# avr-fusebit-doctor-enhanced.net
KiCad netlist of a schematic drawn in EAGLE
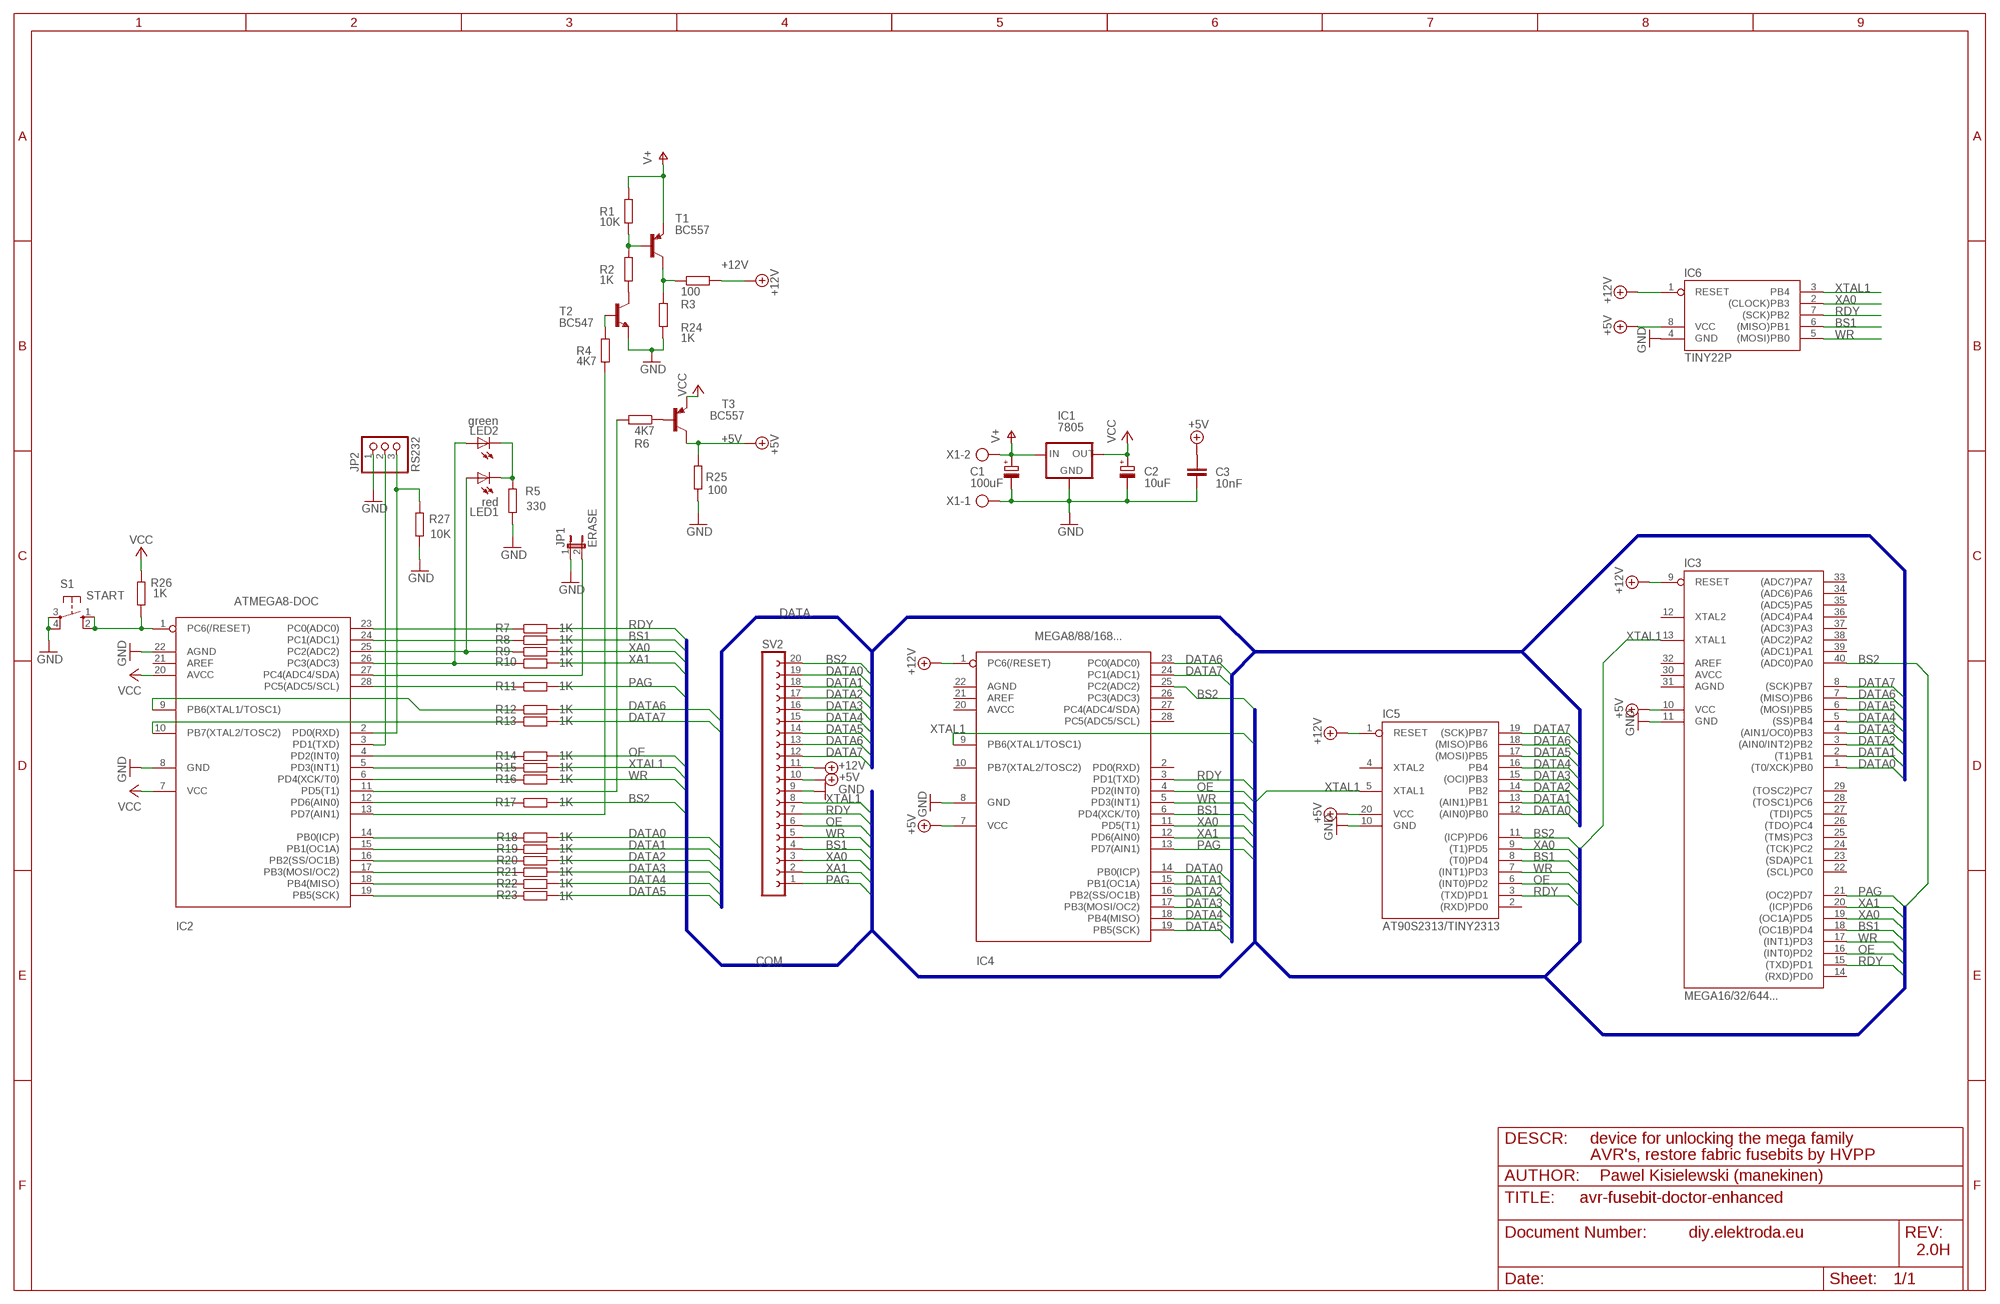
[diagram p0: schematic, sheet 1]

(export (version "E")
  (design (tool "Eeschema 10.0.6"))
  (components
    (comp (ref "C1")
      (value "100uF")
      (footprint "eagle-import:E2,5-5")
      (libsource (lib "eagle-import") (part "CPOL-EUE2.5-5"))
    )
    (comp (ref "C2")
      (value "10uF")
      (footprint "eagle-import:E2,5-5")
      (libsource (lib "eagle-import") (part "CPOL-EUE2.5-5"))
    )
    (comp (ref "C3")
      (value "10nF")
      (footprint "eagle-import:C050-024X044")
      (libsource (lib "eagle-import") (part "C-EU050-024X044"))
    )
    (comp (ref "IC1")
      (value "7805")
      (footprint "eagle-import:78XXL")
      (libsource (lib "eagle-import") (part "78XXL"))
    )
    (comp (ref "IC2")
      (value "ATMEGA8-DOC")
      (footprint "eagle-import:DIL28-3")
      (libsource (lib "eagle-import") (part "MEGA8-P"))
    )
    (comp (ref "IC3")
      (value "MEGA16/32/644...")
      (footprint "eagle-import:DIL40")
      (libsource (lib "eagle-import") (part "MEGA16-P"))
    )
    (comp (ref "IC4")
      (value "MEGA8/88/168...")
      (footprint "eagle-import:DIL28-3")
      (libsource (lib "eagle-import") (part "MEGA8-P"))
    )
    (comp (ref "IC5")
      (value "AT90S2313/TINY2313")
      (footprint "eagle-import:DIL20")
      (libsource (lib "eagle-import") (part "AT90S2313P"))
    )
    (comp (ref "IC6")
      (value "TINY22P")
      (footprint "eagle-import:DIL08")
      (libsource (lib "eagle-import") (part "TINY22P"))
    )
    (comp (ref "JP1")
      (value "ERASE")
      (footprint "eagle-import:JP1")
      (libsource (lib "eagle-import") (part "JP1E"))
    )
    (comp (ref "JP2")
      (value "RS232")
      (footprint "eagle-import:1X03")
      (libsource (lib "eagle-import") (part "PINHD-1X3"))
    )
    (comp (ref "LED1")
      (value "red")
      (footprint "eagle-import:LED3MM")
      (libsource (lib "eagle-import") (part "LED3MM"))
    )
    (comp (ref "LED2")
      (value "green")
      (footprint "eagle-import:LED3MM")
      (libsource (lib "eagle-import") (part "LED3MM"))
    )
    (comp (ref "R1")
      (value "10K")
      (footprint "eagle-import:0204_5")
      (libsource (lib "eagle-import") (part "R-EU_0204/5"))
    )
    (comp (ref "R2")
      (value "1K")
      (footprint "eagle-import:0204_5")
      (libsource (lib "eagle-import") (part "R-EU_0204/5"))
    )
    (comp (ref "R3")
      (value "100")
      (footprint "eagle-import:0204_5")
      (libsource (lib "eagle-import") (part "R-EU_0204/5"))
    )
    (comp (ref "R4")
      (value "4K7")
      (footprint "eagle-import:0204_5")
      (libsource (lib "eagle-import") (part "R-EU_0204/5"))
    )
    (comp (ref "R5")
      (value "330")
      (footprint "eagle-import:0204_5")
      (libsource (lib "eagle-import") (part "R-EU_0204/5"))
    )
    (comp (ref "R6")
      (value "4K7")
      (footprint "eagle-import:0204_5")
      (libsource (lib "eagle-import") (part "R-EU_0204/5"))
    )
    (comp (ref "R7")
      (value "1K")
      (footprint "eagle-import:0204_5")
      (libsource (lib "eagle-import") (part "R-EU_0204/5"))
    )
    (comp (ref "R8")
      (value "1K")
      (footprint "eagle-import:0204_5")
      (libsource (lib "eagle-import") (part "R-EU_0204/5"))
    )
    (comp (ref "R9")
      (value "1K")
      (footprint "eagle-import:0204_5")
      (libsource (lib "eagle-import") (part "R-EU_0204/5"))
    )
    (comp (ref "R10")
      (value "1K")
      (footprint "eagle-import:0204_5")
      (libsource (lib "eagle-import") (part "R-EU_0204/5"))
    )
    (comp (ref "R11")
      (value "1K")
      (footprint "eagle-import:0204_5")
      (libsource (lib "eagle-import") (part "R-EU_0204/5"))
    )
    (comp (ref "R12")
      (value "1K")
      (footprint "eagle-import:0204_5")
      (libsource (lib "eagle-import") (part "R-EU_0204/5"))
    )
    (comp (ref "R13")
      (value "1K")
      (footprint "eagle-import:0204_5")
      (libsource (lib "eagle-import") (part "R-EU_0204/5"))
    )
    (comp (ref "R14")
      (value "1K")
      (footprint "eagle-import:0204_5")
      (libsource (lib "eagle-import") (part "R-EU_0204/5"))
    )
    (comp (ref "R15")
      (value "1K")
      (footprint "eagle-import:0204_5")
      (libsource (lib "eagle-import") (part "R-EU_0204/5"))
    )
    (comp (ref "R16")
      (value "1K")
      (footprint "eagle-import:0204_5")
      (libsource (lib "eagle-import") (part "R-EU_0204/5"))
    )
    (comp (ref "R17")
      (value "1K")
      (footprint "eagle-import:0204_5")
      (libsource (lib "eagle-import") (part "R-EU_0204/5"))
    )
    (comp (ref "R18")
      (value "1K")
      (footprint "eagle-import:0204_5")
      (libsource (lib "eagle-import") (part "R-EU_0204/5"))
    )
    (comp (ref "R19")
      (value "1K")
      (footprint "eagle-import:0204_5")
      (libsource (lib "eagle-import") (part "R-EU_0204/5"))
    )
    (comp (ref "R20")
      (value "1K")
      (footprint "eagle-import:0204_5")
      (libsource (lib "eagle-import") (part "R-EU_0204/5"))
    )
    (comp (ref "R21")
      (value "1K")
      (footprint "eagle-import:0204_5")
      (libsource (lib "eagle-import") (part "R-EU_0204/5"))
    )
    (comp (ref "R22")
      (value "1K")
      (footprint "eagle-import:0204_5")
      (libsource (lib "eagle-import") (part "R-EU_0204/5"))
    )
    (comp (ref "R23")
      (value "1K")
      (footprint "eagle-import:0204_5")
      (libsource (lib "eagle-import") (part "R-EU_0204/5"))
    )
    (comp (ref "R24")
      (value "1K")
      (footprint "eagle-import:0204_5")
      (libsource (lib "eagle-import") (part "R-EU_0204/5"))
    )
    (comp (ref "R25")
      (value "100")
      (footprint "eagle-import:0204_5")
      (libsource (lib "eagle-import") (part "R-EU_0204/5"))
    )
    (comp (ref "R26")
      (value "1K")
      (footprint "eagle-import:0204_5")
      (libsource (lib "eagle-import") (part "R-EU_0204/5"))
    )
    (comp (ref "R27")
      (value "10K")
      (footprint "eagle-import:0204_5")
      (libsource (lib "eagle-import") (part "R-EU_0204/5"))
    )
    (comp (ref "S1")
      (value "START")
      (footprint "eagle-import:B3F-10XX")
      (libsource (lib "eagle-import") (part "10-XX"))
    )
    (comp (ref "SV2")
      (value "FE20-1")
      (footprint "eagle-import:FE20")
      (libsource (lib "eagle-import") (part "FE20-1"))
    )
    (comp (ref "T1")
      (value "BC557")
      (footprint "eagle-import:TO92-EBC")
      (libsource (lib "eagle-import") (part "-PNP-TO92-EBCBC557C"))
    )
    (comp (ref "T2")
      (value "BC547")
      (footprint "eagle-import:TO92-EBC")
      (libsource (lib "eagle-import") (part "-NPN-TO92-EBCBC547A"))
    )
    (comp (ref "T3")
      (value "BC557")
      (footprint "eagle-import:TO92-EBC")
      (libsource (lib "eagle-import") (part "-PNP-TO92-EBCBC557C"))
    )
    (comp (ref "X1")
      (value "AK500/2")
      (footprint "eagle-import:AK500_2")
      (libsource (lib "eagle-import") (part "AK500/2"))
    )
  )
  (nets
    (net (code "3") (name "+5V") (class "Default")
      (node (ref "C3") (pin "1") (pinfunction "1_1") (pintype "passive"))
      (node (ref "IC3") (pin "10") (pinfunction "VCC_10") (pintype "power_in"))
      (node (ref "IC4") (pin "7") (pinfunction "VCC_7") (pintype "bidirectional"))
      (node (ref "IC5") (pin "20") (pinfunction "VCC_20") (pintype "power_in"))
      (node (ref "IC6") (pin "8") (pinfunction "VCC_8") (pintype "power_in"))
      (node (ref "R25") (pin "2") (pinfunction "2_2") (pintype "passive"))
      (node (ref "SV2") (pin "10") (pinfunction "10_10") (pintype "passive"))
      (node (ref "T3") (pin "C") (pinfunction "C_C") (pintype "passive"))
    )
    (net (code "4") (name "+12V") (class "Default")
      (node (ref "IC3") (pin "9") (pinfunction "RESET_9") (pintype "input"))
      (node (ref "IC4") (pin "1") (pinfunction "PC6(/RESET)_1") (pintype "bidirectional"))
      (node (ref "IC5") (pin "1") (pinfunction "RESET_1") (pintype "bidirectional"))
      (node (ref "IC6") (pin "1") (pinfunction "RESET_1") (pintype "input"))
      (node (ref "R3") (pin "2") (pinfunction "2_2") (pintype "passive"))
      (node (ref "SV2") (pin "11") (pinfunction "11_11") (pintype "passive"))
    )
    (net (code "5") (name "/AGND") (class "Default")
      (node (ref "IC3") (pin "31") (pinfunction "AGND_31") (pintype "power_in"))
    )
    (net (code "6") (name "/AREF") (class "Default")
      (node (ref "IC3") (pin "32") (pinfunction "AREF_32") (pintype "power_in"))
    )
    (net (code "7") (name "/AVCC") (class "Default")
      (node (ref "IC3") (pin "30") (pinfunction "AVCC_30") (pintype "power_in"))
    )
    (net (code "8") (name "/BS1") (class "Default")
      (node (ref "IC3") (pin "18") (pinfunction "(OC1B)PD4_18") (pintype "bidirectional"))
      (node (ref "IC4") (pin "6") (pinfunction "PD4(XCK/T0)_6") (pintype "bidirectional"))
      (node (ref "IC5") (pin "8") (pinfunction "(T0)PD4_8") (pintype "bidirectional"))
      (node (ref "IC6") (pin "6") (pinfunction "(MISO)PB1_6") (pintype "bidirectional"))
      (node (ref "R8") (pin "2") (pinfunction "2_2") (pintype "passive"))
      (node (ref "SV2") (pin "4") (pinfunction "4_4") (pintype "passive"))
    )
    (net (code "9") (name "/BS2") (class "Default")
      (node (ref "IC3") (pin "40") (pinfunction "(ADC0)PA0_40") (pintype "bidirectional"))
      (node (ref "IC4") (pin "25") (pinfunction "PC2(ADC2)_25") (pintype "bidirectional"))
      (node (ref "IC5") (pin "11") (pinfunction "(ICP)PD6_11") (pintype "bidirectional"))
      (node (ref "R17") (pin "2") (pinfunction "2_2") (pintype "passive"))
      (node (ref "SV2") (pin "20") (pinfunction "20_20") (pintype "passive"))
    )
    (net (code "10") (name "/DATA0") (class "Default")
      (node (ref "IC3") (pin "1") (pinfunction "(T0/XCK)PB0_1") (pintype "bidirectional"))
      (node (ref "IC4") (pin "14") (pinfunction "PB0(ICP)_14") (pintype "bidirectional"))
      (node (ref "IC5") (pin "12") (pinfunction "(AIN0)PB0_12") (pintype "bidirectional"))
      (node (ref "R18") (pin "2") (pinfunction "2_2") (pintype "passive"))
      (node (ref "SV2") (pin "19") (pinfunction "19_19") (pintype "passive"))
    )
    (net (code "11") (name "/DATA1") (class "Default")
      (node (ref "IC3") (pin "2") (pinfunction "(T1)PB1_2") (pintype "bidirectional"))
      (node (ref "IC4") (pin "15") (pinfunction "PB1(OC1A)_15") (pintype "bidirectional"))
      (node (ref "IC5") (pin "13") (pinfunction "(AIN1)PB1_13") (pintype "bidirectional"))
      (node (ref "R19") (pin "2") (pinfunction "2_2") (pintype "passive"))
      (node (ref "SV2") (pin "18") (pinfunction "18_18") (pintype "passive"))
    )
    (net (code "12") (name "/DATA2") (class "Default")
      (node (ref "IC3") (pin "3") (pinfunction "(AIN0/INT2)PB2_3") (pintype "bidirectional"))
      (node (ref "IC4") (pin "16") (pinfunction "PB2(SS/OC1B)_16") (pintype "bidirectional"))
      (node (ref "IC5") (pin "14") (pinfunction "PB2_14") (pintype "bidirectional"))
      (node (ref "R20") (pin "2") (pinfunction "2_2") (pintype "passive"))
      (node (ref "SV2") (pin "17") (pinfunction "17_17") (pintype "passive"))
    )
    (net (code "13") (name "/DATA3") (class "Default")
      (node (ref "IC3") (pin "4") (pinfunction "(AIN1/OC0)PB3_4") (pintype "bidirectional"))
      (node (ref "IC4") (pin "17") (pinfunction "PB3(MOSI/OC2)_17") (pintype "bidirectional"))
      (node (ref "IC5") (pin "15") (pinfunction "(OCI)PB3_15") (pintype "bidirectional"))
      (node (ref "R21") (pin "2") (pinfunction "2_2") (pintype "passive"))
      (node (ref "SV2") (pin "16") (pinfunction "16_16") (pintype "passive"))
    )
    (net (code "14") (name "/DATA4") (class "Default")
      (node (ref "IC3") (pin "5") (pinfunction "(SS)PB4_5") (pintype "bidirectional"))
      (node (ref "IC4") (pin "18") (pinfunction "PB4(MISO)_18") (pintype "bidirectional"))
      (node (ref "IC5") (pin "16") (pinfunction "PB4_16") (pintype "bidirectional"))
      (node (ref "R22") (pin "2") (pinfunction "2_2") (pintype "passive"))
      (node (ref "SV2") (pin "15") (pinfunction "15_15") (pintype "passive"))
    )
    (net (code "15") (name "/DATA5") (class "Default")
      (node (ref "IC3") (pin "6") (pinfunction "(MOSI)PB5_6") (pintype "bidirectional"))
      (node (ref "IC4") (pin "19") (pinfunction "PB5(SCK)_19") (pintype "bidirectional"))
      (node (ref "IC5") (pin "17") (pinfunction "(MOSI)PB5_17") (pintype "bidirectional"))
      (node (ref "R23") (pin "2") (pinfunction "2_2") (pintype "passive"))
      (node (ref "SV2") (pin "14") (pinfunction "14_14") (pintype "passive"))
    )
    (net (code "16") (name "/DATA6") (class "Default")
      (node (ref "IC3") (pin "7") (pinfunction "(MISO)PB6_7") (pintype "bidirectional"))
      (node (ref "IC4") (pin "23") (pinfunction "PC0(ADC0)_23") (pintype "bidirectional"))
      (node (ref "IC5") (pin "18") (pinfunction "(MISO)PB6_18") (pintype "bidirectional"))
      (node (ref "R12") (pin "2") (pinfunction "2_2") (pintype "passive"))
      (node (ref "SV2") (pin "13") (pinfunction "13_13") (pintype "passive"))
    )
    (net (code "17") (name "/DATA7") (class "Default")
      (node (ref "IC3") (pin "8") (pinfunction "(SCK)PB7_8") (pintype "bidirectional"))
      (node (ref "IC4") (pin "24") (pinfunction "PC1(ADC1)_24") (pintype "bidirectional"))
      (node (ref "IC5") (pin "19") (pinfunction "(SCK)PB7_19") (pintype "bidirectional"))
      (node (ref "R13") (pin "2") (pinfunction "2_2") (pintype "passive"))
      (node (ref "SV2") (pin "12") (pinfunction "12_12") (pintype "passive"))
    )
    (net (code "18") (name "/OE") (class "Default")
      (node (ref "IC3") (pin "16") (pinfunction "(INT0)PD2_16") (pintype "bidirectional"))
      (node (ref "IC4") (pin "4") (pinfunction "PD2(INT0)_4") (pintype "bidirectional"))
      (node (ref "IC5") (pin "6") (pinfunction "(INT0)PD2_6") (pintype "bidirectional"))
      (node (ref "R14") (pin "2") (pinfunction "2_2") (pintype "passive"))
      (node (ref "SV2") (pin "6") (pinfunction "6_6") (pintype "passive"))
    )
    (net (code "19") (name "/PAG") (class "Default")
      (node (ref "IC3") (pin "21") (pinfunction "(OC2)PD7_21") (pintype "bidirectional"))
      (node (ref "IC4") (pin "13") (pinfunction "PD7(AIN1)_13") (pintype "bidirectional"))
      (node (ref "R11") (pin "2") (pinfunction "2_2") (pintype "passive"))
      (node (ref "SV2") (pin "1") (pinfunction "1_1") (pintype "passive"))
    )
    (net (code "20") (name "/RDY") (class "Default")
      (node (ref "IC3") (pin "15") (pinfunction "(TXD)PD1_15") (pintype "bidirectional"))
      (node (ref "IC4") (pin "3") (pinfunction "PD1(TXD)_3") (pintype "bidirectional"))
      (node (ref "IC5") (pin "3") (pinfunction "(TXD)PD1_3") (pintype "bidirectional"))
      (node (ref "IC6") (pin "7") (pinfunction "(SCK)PB2_7") (pintype "bidirectional"))
      (node (ref "R7") (pin "2") (pinfunction "2_2") (pintype "passive"))
      (node (ref "SV2") (pin "7") (pinfunction "7_7") (pintype "passive"))
    )
    (net (code "21") (name "/WR") (class "Default")
      (node (ref "IC3") (pin "17") (pinfunction "(INT1)PD3_17") (pintype "bidirectional"))
      (node (ref "IC4") (pin "5") (pinfunction "PD3(INT1)_5") (pintype "bidirectional"))
      (node (ref "IC5") (pin "7") (pinfunction "(INT1)PD3_7") (pintype "bidirectional"))
      (node (ref "IC6") (pin "5") (pinfunction "(MOSI)PB0_5") (pintype "bidirectional"))
      (node (ref "R16") (pin "2") (pinfunction "2_2") (pintype "passive"))
      (node (ref "SV2") (pin "5") (pinfunction "5_5") (pintype "passive"))
    )
    (net (code "22") (name "/XA0") (class "Default")
      (node (ref "IC3") (pin "19") (pinfunction "(OC1A)PD5_19") (pintype "bidirectional"))
      (node (ref "IC4") (pin "11") (pinfunction "PD5(T1)_11") (pintype "bidirectional"))
      (node (ref "IC5") (pin "9") (pinfunction "(T1)PD5_9") (pintype "bidirectional"))
      (node (ref "IC6") (pin "2") (pinfunction "(CLOCK)PB3_2") (pintype "bidirectional"))
      (node (ref "R9") (pin "2") (pinfunction "2_2") (pintype "passive"))
      (node (ref "SV2") (pin "3") (pinfunction "3_3") (pintype "passive"))
    )
    (net (code "23") (name "/XA1") (class "Default")
      (node (ref "IC3") (pin "20") (pinfunction "(ICP)PD6_20") (pintype "bidirectional"))
      (node (ref "IC4") (pin "12") (pinfunction "PD6(AIN0)_12") (pintype "bidirectional"))
      (node (ref "R10") (pin "2") (pinfunction "2_2") (pintype "passive"))
      (node (ref "SV2") (pin "2") (pinfunction "2_2") (pintype "passive"))
    )
    (net (code "24") (name "/XTAL1") (class "Default")
      (node (ref "IC3") (pin "13") (pinfunction "XTAL1_13") (pintype "bidirectional"))
      (node (ref "IC4") (pin "9") (pinfunction "PB6(XTAL1/TOSC1)_9") (pintype "bidirectional"))
      (node (ref "IC5") (pin "5") (pinfunction "XTAL1_5") (pintype "bidirectional"))
      (node (ref "IC6") (pin "3") (pinfunction "PB4_3") (pintype "bidirectional"))
      (node (ref "R15") (pin "2") (pinfunction "2_2") (pintype "passive"))
      (node (ref "SV2") (pin "8") (pinfunction "8_8") (pintype "passive"))
    )
    (net (code "27") (name "GND") (class "Default")
      (node (ref "C1") (pin "-") (pinfunction "-_-") (pintype "passive"))
      (node (ref "C2") (pin "-") (pinfunction "-_-") (pintype "passive"))
      (node (ref "C3") (pin "2") (pinfunction "2_2") (pintype "passive"))
      (node (ref "IC1") (pin "GND") (pinfunction "GND_GND") (pintype "input"))
      (node (ref "IC2") (pin "22") (pinfunction "AGND_22") (pintype "bidirectional"))
      (node (ref "IC2") (pin "8") (pinfunction "GND_8") (pintype "bidirectional"))
      (node (ref "IC3") (pin "11") (pinfunction "GND_11") (pintype "power_in"))
      (node (ref "IC4") (pin "8") (pinfunction "GND_8") (pintype "bidirectional"))
      (node (ref "IC5") (pin "10") (pinfunction "GND_10") (pintype "power_in"))
      (node (ref "IC6") (pin "4") (pinfunction "GND_4") (pintype "power_in"))
      (node (ref "JP1") (pin "1") (pinfunction "1_1") (pintype "passive"))
      (node (ref "JP2") (pin "1") (pinfunction "1_1") (pintype "passive"))
      (node (ref "R24") (pin "1") (pinfunction "1_1") (pintype "passive"))
      (node (ref "R25") (pin "1") (pinfunction "1_1") (pintype "passive"))
      (node (ref "R27") (pin "2") (pinfunction "2_2") (pintype "passive"))
      (node (ref "R5") (pin "1") (pinfunction "1_1") (pintype "passive"))
      (node (ref "S1") (pin "3") (pinfunction "P_3") (pintype "passive"))
      (node (ref "S1") (pin "4") (pinfunction "P1_4") (pintype "passive"))
      (node (ref "SV2") (pin "9") (pinfunction "9_9") (pintype "passive"))
      (node (ref "T2") (pin "E") (pinfunction "E_E") (pintype "passive"))
      (node (ref "X1") (pin "1") (pinfunction "KL_1") (pintype "passive"))
    )
    (net (code "28") (name "Net-(IC2-PB0(ICP))") (class "Default")
      (node (ref "IC2") (pin "14") (pinfunction "PB0(ICP)_14") (pintype "bidirectional"))
      (node (ref "R18") (pin "1") (pinfunction "1_1") (pintype "passive"))
    )
    (net (code "29") (name "Net-(IC2-PB1(OC1A))") (class "Default")
      (node (ref "IC2") (pin "15") (pinfunction "PB1(OC1A)_15") (pintype "bidirectional"))
      (node (ref "R19") (pin "1") (pinfunction "1_1") (pintype "passive"))
    )
    (net (code "30") (name "Net-(IC2-PB2(SS{slash}OC1B))") (class "Default")
      (node (ref "IC2") (pin "16") (pinfunction "PB2(SS/OC1B)_16") (pintype "bidirectional"))
      (node (ref "R20") (pin "1") (pinfunction "1_1") (pintype "passive"))
    )
    (net (code "31") (name "Net-(IC2-PB3(MOSI{slash}OC2))") (class "Default")
      (node (ref "IC2") (pin "17") (pinfunction "PB3(MOSI/OC2)_17") (pintype "bidirectional"))
      (node (ref "R21") (pin "1") (pinfunction "1_1") (pintype "passive"))
    )
    (net (code "32") (name "Net-(IC2-PB4(MISO))") (class "Default")
      (node (ref "IC2") (pin "18") (pinfunction "PB4(MISO)_18") (pintype "bidirectional"))
      (node (ref "R22") (pin "1") (pinfunction "1_1") (pintype "passive"))
    )
    (net (code "33") (name "Net-(IC2-PB5(SCK))") (class "Default")
      (node (ref "IC2") (pin "19") (pinfunction "PB5(SCK)_19") (pintype "bidirectional"))
      (node (ref "R23") (pin "1") (pinfunction "1_1") (pintype "passive"))
    )
    (net (code "34") (name "Net-(IC2-PB6(XTAL1{slash}TOSC1))") (class "Default")
      (node (ref "IC2") (pin "9") (pinfunction "PB6(XTAL1/TOSC1)_9") (pintype "bidirectional"))
      (node (ref "R12") (pin "1") (pinfunction "1_1") (pintype "passive"))
    )
    (net (code "35") (name "Net-(IC2-PB7(XTAL2{slash}TOSC2))") (class "Default")
      (node (ref "IC2") (pin "10") (pinfunction "PB7(XTAL2/TOSC2)_10") (pintype "bidirectional"))
      (node (ref "R13") (pin "1") (pinfunction "1_1") (pintype "passive"))
    )
    (net (code "36") (name "Net-(IC2-PC0(ADC0))") (class "Default")
      (node (ref "IC2") (pin "23") (pinfunction "PC0(ADC0)_23") (pintype "bidirectional"))
      (node (ref "R7") (pin "1") (pinfunction "1_1") (pintype "passive"))
    )
    (net (code "37") (name "Net-(IC2-PC1(ADC1))") (class "Default")
      (node (ref "IC2") (pin "24") (pinfunction "PC1(ADC1)_24") (pintype "bidirectional"))
      (node (ref "R8") (pin "1") (pinfunction "1_1") (pintype "passive"))
    )
    (net (code "38") (name "Net-(IC2-PC2(ADC2))") (class "Default")
      (node (ref "IC2") (pin "25") (pinfunction "PC2(ADC2)_25") (pintype "bidirectional"))
      (node (ref "LED1") (pin "A") (pinfunction "A_A") (pintype "passive"))
      (node (ref "R9") (pin "1") (pinfunction "1_1") (pintype "passive"))
    )
    (net (code "39") (name "Net-(IC2-PC3(ADC3))") (class "Default")
      (node (ref "IC2") (pin "26") (pinfunction "PC3(ADC3)_26") (pintype "bidirectional"))
      (node (ref "LED2") (pin "A") (pinfunction "A_A") (pintype "passive"))
      (node (ref "R10") (pin "1") (pinfunction "1_1") (pintype "passive"))
    )
    (net (code "40") (name "Net-(IC2-PC4(ADC4{slash}SDA))") (class "Default")
      (node (ref "IC2") (pin "27") (pinfunction "PC4(ADC4/SDA)_27") (pintype "bidirectional"))
      (node (ref "JP1") (pin "2") (pinfunction "2_2") (pintype "passive"))
    )
    (net (code "41") (name "Net-(IC2-PC5(ADC5{slash}SCL))") (class "Default")
      (node (ref "IC2") (pin "28") (pinfunction "PC5(ADC5/SCL)_28") (pintype "bidirectional"))
      (node (ref "R11") (pin "1") (pinfunction "1_1") (pintype "passive"))
    )
    (net (code "42") (name "Net-(IC2-PC6({slash}RESET))") (class "Default")
      (node (ref "IC2") (pin "1") (pinfunction "PC6(/RESET)_1") (pintype "bidirectional"))
      (node (ref "R26") (pin "1") (pinfunction "1_1") (pintype "passive"))
      (node (ref "S1") (pin "1") (pinfunction "S_1") (pintype "passive"))
      (node (ref "S1") (pin "2") (pinfunction "S1_2") (pintype "passive"))
    )
    (net (code "43") (name "Net-(IC2-PD0(RXD))") (class "Default")
      (node (ref "IC2") (pin "2") (pinfunction "PD0(RXD)_2") (pintype "bidirectional"))
      (node (ref "JP2") (pin "3") (pinfunction "3_3") (pintype "passive"))
      (node (ref "R27") (pin "1") (pinfunction "1_1") (pintype "passive"))
    )
    (net (code "44") (name "Net-(IC2-PD1(TXD))") (class "Default")
      (node (ref "IC2") (pin "3") (pinfunction "PD1(TXD)_3") (pintype "bidirectional"))
      (node (ref "JP2") (pin "2") (pinfunction "2_2") (pintype "passive"))
    )
    (net (code "45") (name "Net-(IC2-PD2(INT0))") (class "Default")
      (node (ref "IC2") (pin "4") (pinfunction "PD2(INT0)_4") (pintype "bidirectional"))
      (node (ref "R14") (pin "1") (pinfunction "1_1") (pintype "passive"))
    )
    (net (code "46") (name "Net-(IC2-PD3(INT1))") (class "Default")
      (node (ref "IC2") (pin "5") (pinfunction "PD3(INT1)_5") (pintype "bidirectional"))
      (node (ref "R15") (pin "1") (pinfunction "1_1") (pintype "passive"))
    )
    (net (code "47") (name "Net-(IC2-PD4(XCK{slash}T0))") (class "Default")
      (node (ref "IC2") (pin "6") (pinfunction "PD4(XCK/T0)_6") (pintype "bidirectional"))
      (node (ref "R16") (pin "1") (pinfunction "1_1") (pintype "passive"))
    )
    (net (code "48") (name "Net-(IC2-PD5(T1))") (class "Default")
      (node (ref "IC2") (pin "11") (pinfunction "PD5(T1)_11") (pintype "bidirectional"))
      (node (ref "R6") (pin "2") (pinfunction "2_2") (pintype "passive"))
    )
    (net (code "49") (name "Net-(IC2-PD6(AIN0))") (class "Default")
      (node (ref "IC2") (pin "12") (pinfunction "PD6(AIN0)_12") (pintype "bidirectional"))
      (node (ref "R17") (pin "1") (pinfunction "1_1") (pintype "passive"))
    )
    (net (code "50") (name "Net-(IC2-PD7(AIN1))") (class "Default")
      (node (ref "IC2") (pin "13") (pinfunction "PD7(AIN1)_13") (pintype "bidirectional"))
      (node (ref "R4") (pin "2") (pinfunction "2_2") (pintype "passive"))
    )
    (net (code "51") (name "Net-(LED1-C)") (class "Default")
      (node (ref "LED1") (pin "K") (pinfunction "C_K") (pintype "passive"))
      (node (ref "LED2") (pin "K") (pinfunction "C_K") (pintype "passive"))
      (node (ref "R5") (pin "2") (pinfunction "2_2") (pintype "passive"))
    )
    (net (code "52") (name "Net-(R1-Pad2)") (class "Default")
      (node (ref "R1") (pin "2") (pinfunction "2_2") (pintype "passive"))
      (node (ref "R2") (pin "1") (pinfunction "1_1") (pintype "passive"))
      (node (ref "T1") (pin "B") (pinfunction "B_B") (pintype "passive"))
    )
    (net (code "53") (name "Net-(R2-Pad2)") (class "Default")
      (node (ref "R2") (pin "2") (pinfunction "2_2") (pintype "passive"))
      (node (ref "T2") (pin "C") (pinfunction "C_C") (pintype "passive"))
    )
    (net (code "54") (name "Net-(R4-Pad1)") (class "Default")
      (node (ref "R4") (pin "1") (pinfunction "1_1") (pintype "passive"))
      (node (ref "T2") (pin "B") (pinfunction "B_B") (pintype "passive"))
    )
    (net (code "55") (name "Net-(R6-Pad1)") (class "Default")
      (node (ref "R6") (pin "1") (pinfunction "1_1") (pintype "passive"))
      (node (ref "T3") (pin "B") (pinfunction "B_B") (pintype "passive"))
    )
    (net (code "56") (name "Net-(R24-Pad2)") (class "Default")
      (node (ref "R24") (pin "2") (pinfunction "2_2") (pintype "passive"))
      (node (ref "R3") (pin "1") (pinfunction "1_1") (pintype "passive"))
      (node (ref "T1") (pin "C") (pinfunction "C_C") (pintype "passive"))
    )
    (net (code "57") (name "V+") (class "Default")
      (node (ref "C1") (pin "+") (pinfunction "+_+") (pintype "passive"))
      (node (ref "IC1") (pin "IN") (pinfunction "IN_IN") (pintype "input"))
      (node (ref "R1") (pin "1") (pinfunction "1_1") (pintype "passive"))
      (node (ref "T1") (pin "E") (pinfunction "E_E") (pintype "passive"))
      (node (ref "X1") (pin "2") (pinfunction "KL_2") (pintype "passive"))
    )
    (net (code "58") (name "VCC") (class "Default")
      (node (ref "C2") (pin "+") (pinfunction "+_+") (pintype "passive"))
      (node (ref "IC1") (pin "OUT") (pinfunction "OUT_OUT") (pintype "passive"))
      (node (ref "IC2") (pin "20") (pinfunction "AVCC_20") (pintype "bidirectional"))
      (node (ref "IC2") (pin "7") (pinfunction "VCC_7") (pintype "bidirectional"))
      (node (ref "R26") (pin "2") (pinfunction "2_2") (pintype "passive"))
      (node (ref "T3") (pin "E") (pinfunction "E_E") (pintype "passive"))
    )
    (net (code "59") (name "unconnected-(IC2-AREF-Pad21)") (class "Default")
      (node (ref "IC2") (pin "21") (pinfunction "AREF_21") (pintype "bidirectional"))
    )
    (net (code "60") (name "unconnected-(IC3-(ADC1)PA1-Pad39)") (class "Default")
      (node (ref "IC3") (pin "39") (pinfunction "(ADC1)PA1_39") (pintype "bidirectional"))
    )
    (net (code "61") (name "unconnected-(IC3-(ADC2)PA2-Pad38)") (class "Default")
      (node (ref "IC3") (pin "38") (pinfunction "(ADC2)PA2_38") (pintype "bidirectional"))
    )
    (net (code "62") (name "unconnected-(IC3-(ADC3)PA3-Pad37)") (class "Default")
      (node (ref "IC3") (pin "37") (pinfunction "(ADC3)PA3_37") (pintype "bidirectional"))
    )
    (net (code "63") (name "unconnected-(IC3-(ADC4)PA4-Pad36)") (class "Default")
      (node (ref "IC3") (pin "36") (pinfunction "(ADC4)PA4_36") (pintype "bidirectional"))
    )
    (net (code "64") (name "unconnected-(IC3-(ADC5)PA5-Pad35)") (class "Default")
      (node (ref "IC3") (pin "35") (pinfunction "(ADC5)PA5_35") (pintype "bidirectional"))
    )
    (net (code "65") (name "unconnected-(IC3-(ADC6)PA6-Pad34)") (class "Default")
      (node (ref "IC3") (pin "34") (pinfunction "(ADC6)PA6_34") (pintype "bidirectional"))
    )
    (net (code "66") (name "unconnected-(IC3-(ADC7)PA7-Pad33)") (class "Default")
      (node (ref "IC3") (pin "33") (pinfunction "(ADC7)PA7_33") (pintype "bidirectional"))
    )
    (net (code "67") (name "unconnected-(IC3-(RXD)PD0-Pad14)") (class "Default")
      (node (ref "IC3") (pin "14") (pinfunction "(RXD)PD0_14") (pintype "bidirectional"))
    )
    (net (code "68") (name "unconnected-(IC3-(SCL)PC0-Pad22)") (class "Default")
      (node (ref "IC3") (pin "22") (pinfunction "(SCL)PC0_22") (pintype "bidirectional"))
    )
    (net (code "69") (name "unconnected-(IC3-(SDA)PC1-Pad23)") (class "Default")
      (node (ref "IC3") (pin "23") (pinfunction "(SDA)PC1_23") (pintype "bidirectional"))
    )
    (net (code "70") (name "unconnected-(IC3-(TCK)PC2-Pad24)") (class "Default")
      (node (ref "IC3") (pin "24") (pinfunction "(TCK)PC2_24") (pintype "bidirectional"))
    )
    (net (code "71") (name "unconnected-(IC3-(TDI)PC5-Pad27)") (class "Default")
      (node (ref "IC3") (pin "27") (pinfunction "(TDI)PC5_27") (pintype "bidirectional"))
    )
    (net (code "72") (name "unconnected-(IC3-(TDO)PC4-Pad26)") (class "Default")
      (node (ref "IC3") (pin "26") (pinfunction "(TDO)PC4_26") (pintype "bidirectional"))
    )
    (net (code "73") (name "unconnected-(IC3-(TMS)PC3-Pad25)") (class "Default")
      (node (ref "IC3") (pin "25") (pinfunction "(TMS)PC3_25") (pintype "bidirectional"))
    )
    (net (code "74") (name "unconnected-(IC3-(TOSC1)PC6-Pad28)") (class "Default")
      (node (ref "IC3") (pin "28") (pinfunction "(TOSC1)PC6_28") (pintype "bidirectional"))
    )
    (net (code "75") (name "unconnected-(IC3-(TOSC2)PC7-Pad29)") (class "Default")
      (node (ref "IC3") (pin "29") (pinfunction "(TOSC2)PC7_29") (pintype "bidirectional"))
    )
    (net (code "76") (name "unconnected-(IC3-XTAL2-Pad12)") (class "Default")
      (node (ref "IC3") (pin "12") (pinfunction "XTAL2_12") (pintype "bidirectional"))
    )
    (net (code "77") (name "unconnected-(IC4-AGND-Pad22)") (class "Default")
      (node (ref "IC4") (pin "22") (pinfunction "AGND_22") (pintype "bidirectional"))
    )
    (net (code "78") (name "unconnected-(IC4-AREF-Pad21)") (class "Default")
      (node (ref "IC4") (pin "21") (pinfunction "AREF_21") (pintype "bidirectional"))
    )
    (net (code "79") (name "unconnected-(IC4-AVCC-Pad20)") (class "Default")
      (node (ref "IC4") (pin "20") (pinfunction "AVCC_20") (pintype "bidirectional"))
    )
    (net (code "80") (name "unconnected-(IC4-PB7(XTAL2{slash}TOSC2)-Pad10)") (class "Default")
      (node (ref "IC4") (pin "10") (pinfunction "PB7(XTAL2/TOSC2)_10") (pintype "bidirectional"))
    )
    (net (code "81") (name "unconnected-(IC4-PC3(ADC3)-Pad26)") (class "Default")
      (node (ref "IC4") (pin "26") (pinfunction "PC3(ADC3)_26") (pintype "bidirectional"))
    )
    (net (code "82") (name "unconnected-(IC4-PC4(ADC4{slash}SDA)-Pad27)") (class "Default")
      (node (ref "IC4") (pin "27") (pinfunction "PC4(ADC4/SDA)_27") (pintype "bidirectional"))
    )
    (net (code "83") (name "unconnected-(IC4-PC5(ADC5{slash}SCL)-Pad28)") (class "Default")
      (node (ref "IC4") (pin "28") (pinfunction "PC5(ADC5/SCL)_28") (pintype "bidirectional"))
    )
    (net (code "84") (name "unconnected-(IC4-PD0(RXD)-Pad2)") (class "Default")
      (node (ref "IC4") (pin "2") (pinfunction "PD0(RXD)_2") (pintype "bidirectional"))
    )
    (net (code "85") (name "unconnected-(IC5-(RXD)PD0-Pad2)") (class "Default")
      (node (ref "IC5") (pin "2") (pinfunction "(RXD)PD0_2") (pintype "bidirectional"))
    )
    (net (code "86") (name "unconnected-(IC5-XTAL2-Pad4)") (class "Default")
      (node (ref "IC5") (pin "4") (pinfunction "XTAL2_4") (pintype "bidirectional"))
    )
  )
)
